# sensor_node_v0_03.net
KiCad netlist of a schematic drawn in EAGLE
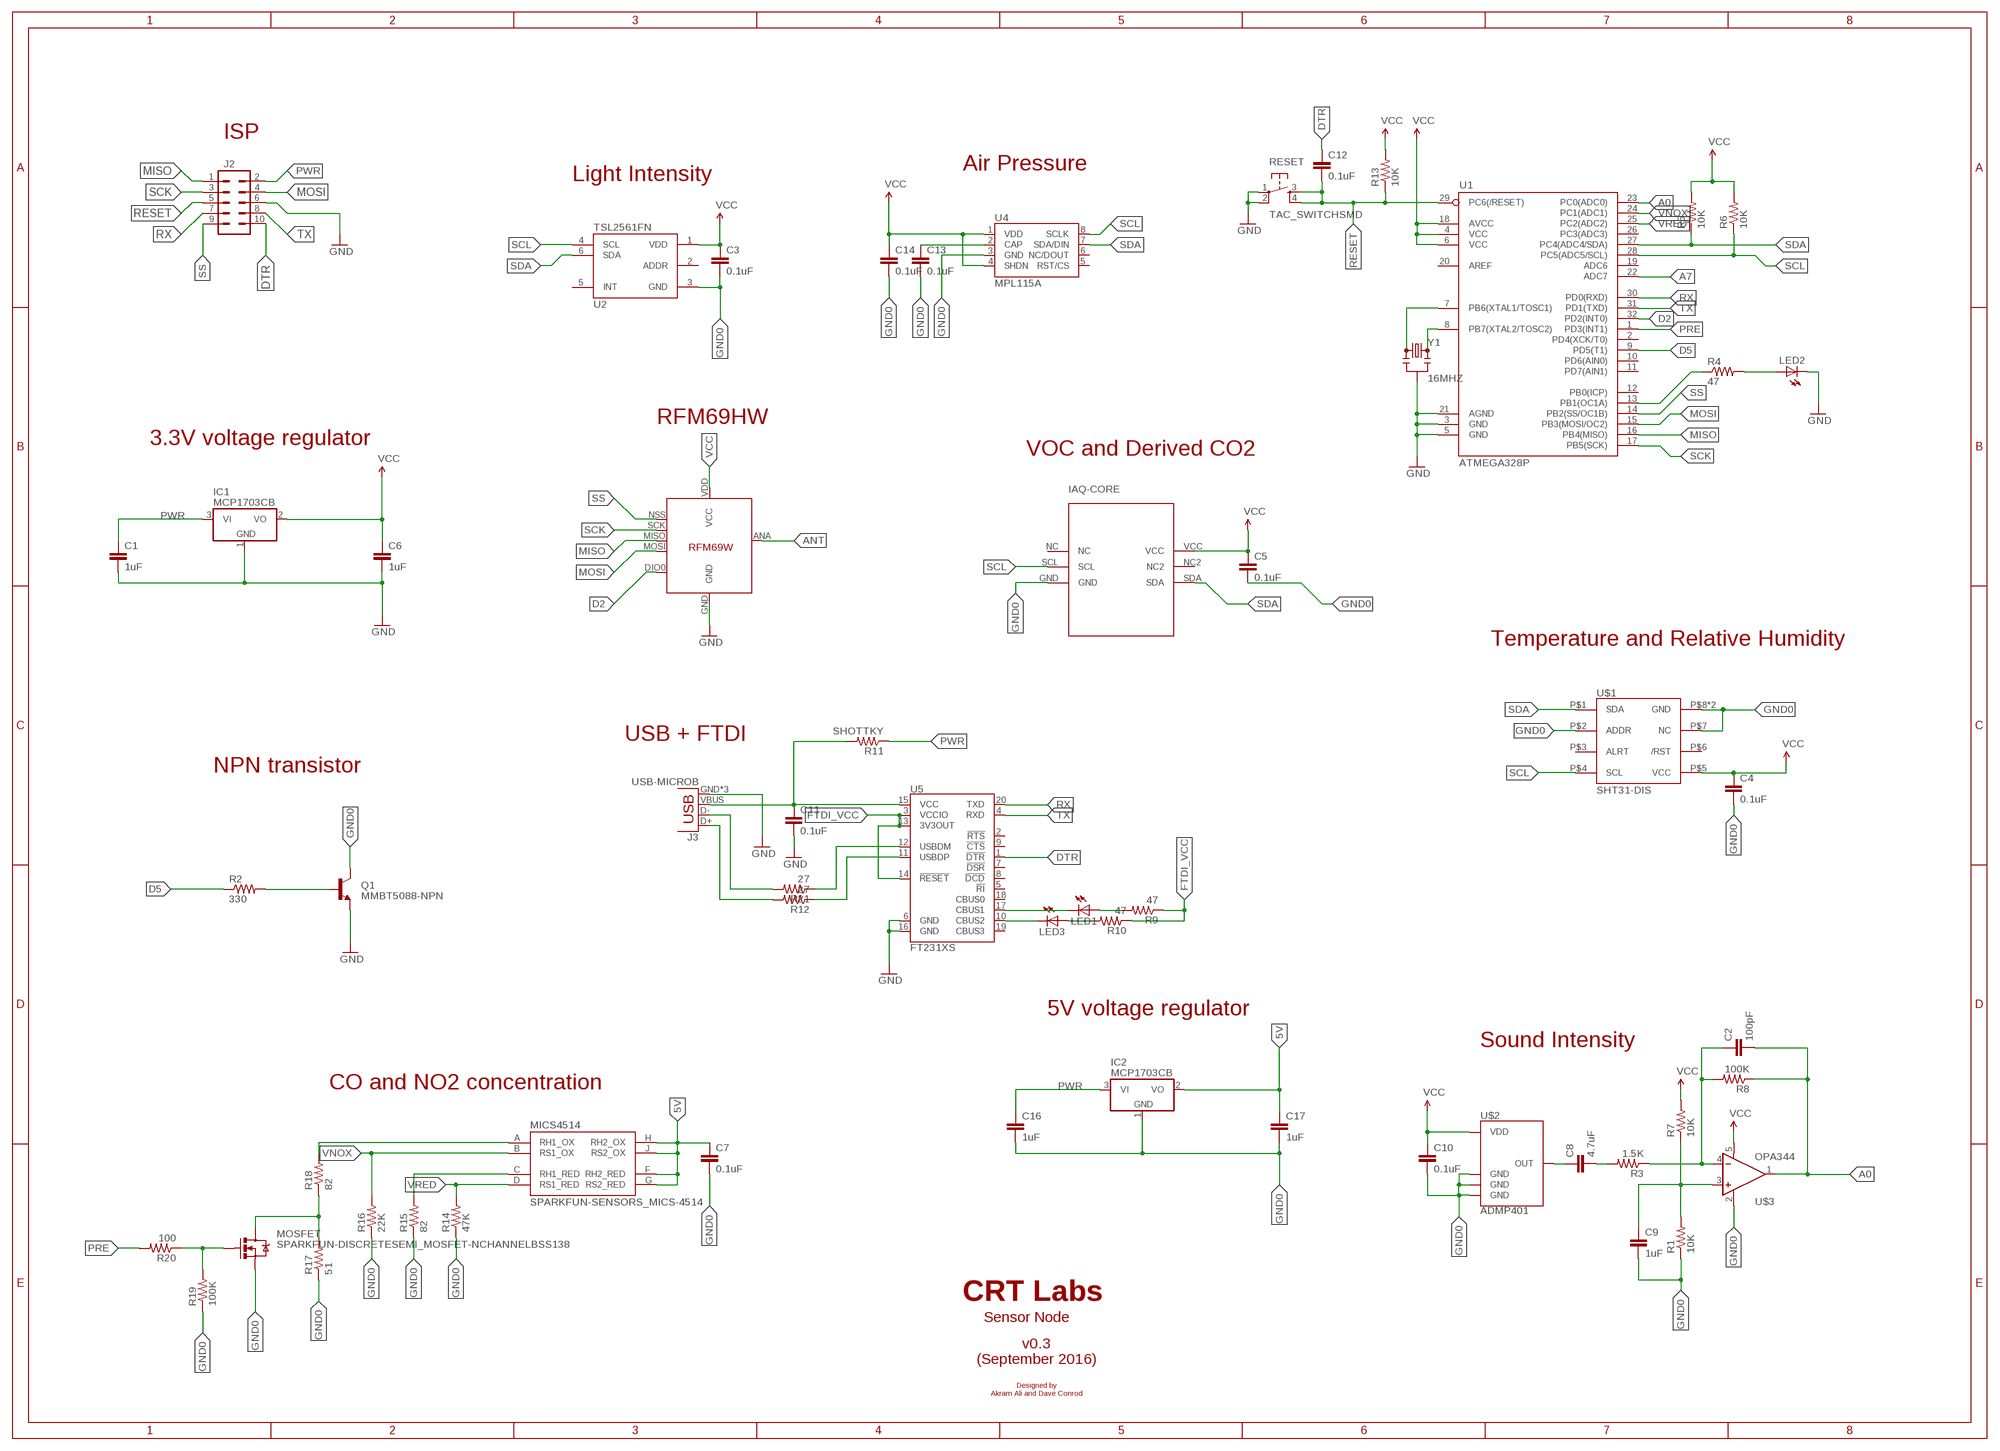
[diagram p0: schematic, sheet 1]

(export (version "E")
  (design (tool "Eeschema 10.0.6"))
  (components
    (comp (ref "C1")
      (value "1uF")
      (footprint "eagle-import:0805")
      (libsource (lib "eagle-import") (part "CAP0805"))
    )
    (comp (ref "C2")
      (value "100pF")
      (footprint "eagle-import:0805")
      (libsource (lib "eagle-import") (part "CAP0805"))
    )
    (comp (ref "C3")
      (value "0.1uF")
      (footprint "eagle-import:0805")
      (libsource (lib "eagle-import") (part "SparkFun-Passives_CAP0805"))
    )
    (comp (ref "C4")
      (value "0.1uF")
      (footprint "eagle-import:0805")
      (libsource (lib "eagle-import") (part "SparkFun-Passives_CAP0805"))
    )
    (comp (ref "C5")
      (value "0.1uF")
      (footprint "eagle-import:0805")
      (libsource (lib "eagle-import") (part "SparkFun-Passives_CAP0805"))
    )
    (comp (ref "C6")
      (value "1uF")
      (footprint "eagle-import:0805")
      (libsource (lib "eagle-import") (part "CAP0805"))
    )
    (comp (ref "C7")
      (value "0.1uF")
      (footprint "eagle-import:0805")
      (libsource (lib "eagle-import") (part "SparkFun-Passives_CAP0805"))
    )
    (comp (ref "C8")
      (value "4.7uF")
      (footprint "eagle-import:0805")
      (libsource (lib "eagle-import") (part "CAP0805"))
    )
    (comp (ref "C9")
      (value "1uF")
      (footprint "eagle-import:0805")
      (libsource (lib "eagle-import") (part "CAP0805"))
    )
    (comp (ref "C10")
      (value "0.1uF")
      (footprint "eagle-import:0805")
      (libsource (lib "eagle-import") (part "CAP0805"))
    )
    (comp (ref "C11")
      (value "0.1uF")
      (footprint "eagle-import:0805")
      (libsource (lib "eagle-import") (part "CAP0805"))
    )
    (comp (ref "C12")
      (value "0.1uF")
      (footprint "eagle-import:0805")
      (libsource (lib "eagle-import") (part "SparkFun-Passives_CAP0805"))
    )
    (comp (ref "C13")
      (value "0.1uF")
      (footprint "eagle-import:0805")
      (libsource (lib "eagle-import") (part "SparkFun-Passives_CAP0805"))
    )
    (comp (ref "C14")
      (value "0.1uF")
      (footprint "eagle-import:0805")
      (libsource (lib "eagle-import") (part "SparkFun-Passives_CAP0805"))
    )
    (comp (ref "C16")
      (value "1uF")
      (footprint "eagle-import:0805")
      (libsource (lib "eagle-import") (part "CAP0805"))
    )
    (comp (ref "C17")
      (value "1uF")
      (footprint "eagle-import:0805")
      (libsource (lib "eagle-import") (part "CAP0805"))
    )
    (comp (ref "IAQ-CORE")
      (value "IAQ-CORE")
      (footprint "eagle-import:IAQ-CORE")
      (fields (field (name "MPN") "IAQ CORE"))
      (libsource (lib "eagle-import") (part "IAQ-CORE"))
    )
    (comp (ref "IC1")
      (value "MCP1703CB")
      (footprint "eagle-import:SOT23")
      (fields (field (name "MPN") "MCP1703T-2502E/CB"))
      (libsource (lib "eagle-import") (part "MCP1703CB"))
    )
    (comp (ref "IC2")
      (value "MCP1703CB")
      (footprint "eagle-import:SOT23")
      (fields (field (name "MPN") "MCP1703T-2502E/CB"))
      (libsource (lib "eagle-import") (part "MCP1703CB"))
    )
    (comp (ref "J2")
      (value "M05X2PTH")
      (footprint "eagle-import:AVR_ICSP")
      (libsource (lib "eagle-import") (part "M05X2PTH"))
    )
    (comp (ref "J3")
      (value "USB-MICROB")
      (footprint "eagle-import:USB-MICROB")
      (libsource (lib "eagle-import") (part "USB-MICROB"))
    )
    (comp (ref "LED1")
      (value "LEDCHIPLED_0805")
      (footprint "eagle-import:CHIPLED_0805")
      (libsource (lib "eagle-import") (part "LEDCHIPLED_0805"))
    )
    (comp (ref "LED2")
      (value "LEDCHIPLED_0805")
      (footprint "eagle-import:CHIPLED_0805")
      (libsource (lib "eagle-import") (part "LEDCHIPLED_0805"))
    )
    (comp (ref "LED3")
      (value "LEDCHIPLED_0805")
      (footprint "eagle-import:CHIPLED_0805")
      (libsource (lib "eagle-import") (part "LEDCHIPLED_0805"))
    )
    (comp (ref "MICS4514")
      (value "SPARKFUN-SENSORS_MICS-4514")
      (footprint "eagle-import:SPARKFUN-SENSORS_MICS_10-SMD")
      (libsource (lib "eagle-import") (part "SPARKFUN-SENSORS_MICS-4514"))
    )
    (comp (ref "MOSFET")
      (value "SPARKFUN-DISCRETESEMI_MOSFET-NCHANNELBSS138")
      (footprint "eagle-import:SPARKFUN-DISCRETESEMI_SOT23-3")
      (libsource (lib "eagle-import") (part "SPARKFUN-DISCRETESEMI_MOSFET-NCHANNELBSS138"))
    )
    (comp (ref "Q1")
      (value "MMBT5088-NPN")
      (footprint "eagle-import:SOT23-3")
      (libsource (lib "eagle-import") (part "TRANSISTOR_NPNMMBT5088"))
    )
    (comp (ref "R1")
      (value "10K")
      (footprint "eagle-import:0805")
      (libsource (lib "eagle-import") (part "RESISTOR0805-RES"))
    )
    (comp (ref "R2")
      (value "330")
      (footprint "eagle-import:0805")
      (libsource (lib "eagle-import") (part "RESISTOR0805-RES"))
    )
    (comp (ref "R3")
      (value "1.5K")
      (footprint "eagle-import:0805")
      (libsource (lib "eagle-import") (part "RESISTOR0805-RES"))
    )
    (comp (ref "R4")
      (value "47")
      (footprint "eagle-import:0805")
      (libsource (lib "eagle-import") (part "SparkFun-Resistors_RESISTOR0805-RES"))
    )
    (comp (ref "R5")
      (value "10K")
      (footprint "eagle-import:0805")
      (libsource (lib "eagle-import") (part "SparkFun-Resistors_RESISTOR0805-RES"))
    )
    (comp (ref "R6")
      (value "10K")
      (footprint "eagle-import:0805")
      (libsource (lib "eagle-import") (part "SparkFun-Resistors_RESISTOR0805-RES"))
    )
    (comp (ref "R7")
      (value "10K")
      (footprint "eagle-import:0805")
      (libsource (lib "eagle-import") (part "RESISTOR0805-RES"))
    )
    (comp (ref "R8")
      (value "100K")
      (footprint "eagle-import:0805")
      (libsource (lib "eagle-import") (part "RESISTOR0805-RES"))
    )
    (comp (ref "R9")
      (value "47")
      (footprint "eagle-import:0805")
      (libsource (lib "eagle-import") (part "RESISTOR0805-RES"))
    )
    (comp (ref "R10")
      (value "47")
      (footprint "eagle-import:0805")
      (libsource (lib "eagle-import") (part "RESISTOR0805-RES"))
    )
    (comp (ref "R11")
      (value "SHOTTKY")
      (footprint "eagle-import:0805")
      (libsource (lib "eagle-import") (part "RESISTOR0805-RES"))
    )
    (comp (ref "R12")
      (value "27")
      (footprint "eagle-import:0805")
      (libsource (lib "eagle-import") (part "RESISTOR0805-RES"))
    )
    (comp (ref "R13")
      (value "10K")
      (footprint "eagle-import:0805")
      (libsource (lib "eagle-import") (part "RESISTOR0805-RES"))
    )
    (comp (ref "R14")
      (value "47K")
      (footprint "eagle-import:0805")
      (libsource (lib "eagle-import") (part "RESISTOR0805-RES"))
    )
    (comp (ref "R15")
      (value "82")
      (footprint "eagle-import:0805")
      (libsource (lib "eagle-import") (part "RESISTOR0805-RES"))
    )
    (comp (ref "R16")
      (value "22K")
      (footprint "eagle-import:0805")
      (libsource (lib "eagle-import") (part "RESISTOR0805-RES"))
    )
    (comp (ref "R17")
      (value "51")
      (footprint "eagle-import:0805")
      (libsource (lib "eagle-import") (part "RESISTOR0805-RES"))
    )
    (comp (ref "R18")
      (value "82")
      (footprint "eagle-import:0805")
      (libsource (lib "eagle-import") (part "RESISTOR0805-RES"))
    )
    (comp (ref "R19")
      (value "100K")
      (footprint "eagle-import:0805")
      (libsource (lib "eagle-import") (part "RESISTOR0805-RES"))
    )
    (comp (ref "R20")
      (value "100")
      (footprint "eagle-import:0805")
      (libsource (lib "eagle-import") (part "RESISTOR0805-RES"))
    )
    (comp (ref "R21")
      (value "27")
      (footprint "eagle-import:0805")
      (libsource (lib "eagle-import") (part "RESISTOR0805-RES"))
    )
    (comp (ref "RESET")
      (value "TAC_SWITCHSMD")
      (footprint "eagle-import:TACTILE-SWITCH-SMD")
      (libsource (lib "eagle-import") (part "TAC_SWITCHSMD"))
    )
    (comp (ref "U$1")
      (value "SHT31-DIS")
      (footprint "eagle-import:SHT3X")
      (fields (field (name "MPN") "SHT31-DIS-B"))
      (libsource (lib "eagle-import") (part "SHT31-DIS"))
    )
    (comp (ref "U$2")
      (value "ADMP401")
      (footprint "eagle-import:ADMP401")
      (libsource (lib "eagle-import") (part "ADMP401"))
    )
    (comp (ref "U$3")
      (value "OPA344")
      (footprint "eagle-import:SOT23-5")
      (libsource (lib "eagle-import") (part "OPA344"))
    )
    (comp (ref "U$4")
      (value "RFM69HW")
      (footprint "eagle-import:LOWPOWERLAB_RFM69W-MINPADS")
      (libsource (lib "eagle-import") (part "LOWPOWERLAB_RFM69"))
    )
    (comp (ref "U1")
      (value "ATMEGA328P")
      (footprint "eagle-import:TQFP32-08")
      (fields (field (name "MPN") "ATMEGA328PB-AU"))
      (libsource (lib "eagle-import") (part "ATMEGA328P_TQFP"))
    )
    (comp (ref "U2")
      (value "TSL2561FN")
      (footprint "eagle-import:FN-6")
      (fields (field (name "MANF") "AMS-TAOS-USA-Inc."))
      (libsource (lib "eagle-import") (part "TSL2561FN"))
    )
    (comp (ref "U4")
      (value "MPL115A")
      (footprint "eagle-import:LGA8")
      (libsource (lib "eagle-import") (part "MPL115A"))
    )
    (comp (ref "U5")
      (value "FT231XS")
      (footprint "eagle-import:SSOP20_L")
      (libsource (lib "eagle-import") (part "FT231XS"))
    )
    (comp (ref "Y1")
      (value "16MHZ")
      (footprint "eagle-import:RESONATOR-SMD")
      (libsource (lib "eagle-import") (part "RESONATOR16MHZ"))
    )
  )
  (nets
    (net (code "1") (name "5V") (class "Default")
      (node (ref "C17") (pin "1") (pinfunction "1_1") (pintype "passive"))
      (node (ref "C7") (pin "1") (pinfunction "1_1") (pintype "passive"))
      (node (ref "IC2") (pin "2") (pinfunction "VO_2") (pintype "passive"))
      (node (ref "MICS4514") (pin "F") (pinfunction "RH2_RED_F") (pintype "bidirectional"))
      (node (ref "MICS4514") (pin "G") (pinfunction "RS2_RED_G") (pintype "bidirectional"))
      (node (ref "MICS4514") (pin "H") (pinfunction "RH2_OX_H") (pintype "bidirectional"))
      (node (ref "MICS4514") (pin "J") (pinfunction "RS2_OX_J") (pintype "bidirectional"))
    )
    (net (code "2") (name "A0") (class "Default")
      (node (ref "C2") (pin "2") (pinfunction "2_2") (pintype "passive"))
      (node (ref "R8") (pin "1") (pinfunction "1_1") (pintype "passive"))
      (node (ref "U$3") (pin "1") (pinfunction "OUT_1") (pintype "output"))
      (node (ref "U1") (pin "23") (pinfunction "PC0(ADC0)_23") (pintype "bidirectional"))
    )
    (net (code "3") (name "A7") (class "Default")
      (node (ref "U1") (pin "22") (pinfunction "ADC7_22") (pintype "bidirectional"))
    )
    (net (code "4") (name "ANT") (class "Default")
      (node (ref "U$4") (pin "ANA") (pinfunction "ANT_ANA") (pintype "passive"))
    )
    (net (code "5") (name "D2") (class "Default")
      (node (ref "U$4") (pin "DIO0") (pinfunction "DIO0_DIO0") (pintype "open_collector"))
      (node (ref "U1") (pin "32") (pinfunction "PD2(INT0)_32") (pintype "bidirectional"))
    )
    (net (code "6") (name "D5") (class "Default")
      (node (ref "R2") (pin "1") (pinfunction "1_1") (pintype "passive"))
      (node (ref "U1") (pin "9") (pinfunction "PD5(T1)_9") (pintype "bidirectional"))
    )
    (net (code "7") (name "DTR") (class "Default")
      (node (ref "C12") (pin "1") (pinfunction "1_1") (pintype "passive"))
      (node (ref "J2") (pin "10") (pinfunction "10_10") (pintype "passive"))
      (node (ref "U5") (pin "1") (pinfunction "~{DTR}_1") (pintype "bidirectional"))
    )
    (net (code "8") (name "FTDI_VCC") (class "Default")
      (node (ref "R10") (pin "1") (pinfunction "1_1") (pintype "passive"))
      (node (ref "R9") (pin "1") (pinfunction "1_1") (pintype "passive"))
      (node (ref "U5") (pin "13") (pinfunction "3V3OUT_13") (pintype "bidirectional"))
      (node (ref "U5") (pin "14") (pinfunction "~{RESET}_14") (pintype "bidirectional"))
      (node (ref "U5") (pin "3") (pinfunction "VCCIO_3") (pintype "bidirectional"))
    )
    (net (code "9") (name "GND") (class "Default")
      (node (ref "C1") (pin "2") (pinfunction "2_2") (pintype "passive"))
      (node (ref "C11") (pin "2") (pinfunction "2_2") (pintype "passive"))
      (node (ref "C6") (pin "2") (pinfunction "2_2") (pintype "passive"))
      (node (ref "IC1") (pin "1") (pinfunction "GND_1") (pintype "passive"))
      (node (ref "J2") (pin "6") (pinfunction "6_6") (pintype "passive"))
      (node (ref "J3") (pin "GND") (pinfunction "GND_GND") (pintype "bidirectional"))
      (node (ref "J3") (pin "MT1") (pinfunction "GND_MT1") (pintype "bidirectional"))
      (node (ref "J3") (pin "MT2") (pinfunction "GND_MT2") (pintype "bidirectional"))
      (node (ref "LED2") (pin "C") (pinfunction "C_C") (pintype "passive"))
      (node (ref "Q1") (pin "2") (pinfunction "E_2") (pintype "passive"))
      (node (ref "RESET") (pin "1") (pinfunction "1_1") (pintype "passive"))
      (node (ref "RESET") (pin "2") (pinfunction "2_2") (pintype "passive"))
      (node (ref "U$4") (pin "GND") (pinfunction "GND_GND") (pintype "power_in"))
      (node (ref "U1") (pin "21") (pinfunction "AGND_21") (pintype "bidirectional"))
      (node (ref "U1") (pin "3") (pinfunction "GND_3") (pintype "bidirectional"))
      (node (ref "U1") (pin "5") (pinfunction "GND_5") (pintype "bidirectional"))
      (node (ref "U5") (pin "16") (pinfunction "GND_16") (pintype "bidirectional"))
      (node (ref "U5") (pin "6") (pinfunction "GND_6") (pintype "bidirectional"))
      (node (ref "Y1") (pin "2") (pinfunction "2_2") (pintype "passive"))
    )
    (net (code "10") (name "GND0") (class "Default")
      (node (ref "C10") (pin "2") (pinfunction "2_2") (pintype "passive"))
      (node (ref "C13") (pin "2") (pinfunction "2_2") (pintype "passive"))
      (node (ref "C14") (pin "2") (pinfunction "2_2") (pintype "passive"))
      (node (ref "C16") (pin "2") (pinfunction "2_2") (pintype "passive"))
      (node (ref "C17") (pin "2") (pinfunction "2_2") (pintype "passive"))
      (node (ref "C3") (pin "2") (pinfunction "2_2") (pintype "passive"))
      (node (ref "C4") (pin "2") (pinfunction "2_2") (pintype "passive"))
      (node (ref "C5") (pin "2") (pinfunction "2_2") (pintype "passive"))
      (node (ref "C7") (pin "2") (pinfunction "2_2") (pintype "passive"))
      (node (ref "C9") (pin "2") (pinfunction "2_2") (pintype "passive"))
      (node (ref "IAQ-CORE") (pin "GND") (pinfunction "GND_GND") (pintype "bidirectional"))
      (node (ref "IC2") (pin "1") (pinfunction "GND_1") (pintype "passive"))
      (node (ref "MOSFET") (pin "2") (pinfunction "S_2") (pintype "passive"))
      (node (ref "Q1") (pin "3") (pinfunction "C_3") (pintype "passive"))
      (node (ref "R1") (pin "1") (pinfunction "1_1") (pintype "passive"))
      (node (ref "R14") (pin "1") (pinfunction "1_1") (pintype "passive"))
      (node (ref "R15") (pin "1") (pinfunction "1_1") (pintype "passive"))
      (node (ref "R16") (pin "1") (pinfunction "1_1") (pintype "passive"))
      (node (ref "R17") (pin "1") (pinfunction "1_1") (pintype "passive"))
      (node (ref "R19") (pin "1") (pinfunction "1_1") (pintype "passive"))
      (node (ref "U$1") (pin "P$2") (pinfunction "ADDR_P$2") (pintype "bidirectional"))
      (node (ref "U$1") (pin "P$7") (pinfunction "NC_P$7") (pintype "bidirectional"))
      (node (ref "U$1") (pin "P$8") (pinfunction "GND_P$8") (pintype "bidirectional"))
      (node (ref "U$1") (pin "PAD") (pinfunction "GND_PAD") (pintype "bidirectional"))
      (node (ref "U$2") (pin "2") (pinfunction "GND_2") (pintype "bidirectional"))
      (node (ref "U$2") (pin "4") (pinfunction "GND_4") (pintype "bidirectional"))
      (node (ref "U$2") (pin "6") (pinfunction "GND_6") (pintype "bidirectional"))
      (node (ref "U$3") (pin "2") (pinfunction "V-_2") (pintype "power_in"))
      (node (ref "U2") (pin "3") (pinfunction "GND_3") (pintype "power_in"))
      (node (ref "U4") (pin "3") (pinfunction "GND_3") (pintype "bidirectional"))
    )
    (net (code "11") (name "MISO") (class "Default")
      (node (ref "J2") (pin "1") (pinfunction "1_1") (pintype "passive"))
      (node (ref "U$4") (pin "MISO") (pinfunction "MISO_MISO") (pintype "input"))
      (node (ref "U1") (pin "16") (pinfunction "PB4(MISO)_16") (pintype "bidirectional"))
    )
    (net (code "12") (name "MOSI") (class "Default")
      (node (ref "J2") (pin "4") (pinfunction "4_4") (pintype "passive"))
      (node (ref "U$4") (pin "MOSI") (pinfunction "MOSI_MOSI") (pintype "output"))
      (node (ref "U1") (pin "15") (pinfunction "PB3(MOSI/OC2)_15") (pintype "bidirectional"))
    )
    (net (code "13") (name "Net-(C8-Pad2)") (class "Default")
      (node (ref "C8") (pin "2") (pinfunction "2_2") (pintype "passive"))
      (node (ref "R3") (pin "2") (pinfunction "2_2") (pintype "passive"))
    )
    (net (code "14") (name "Net-(J3-PadD+)") (class "Default")
      (node (ref "J3") (pin "D+") (pinfunction "D+_D+") (pintype "bidirectional"))
      (node (ref "R12") (pin "2") (pinfunction "2_2") (pintype "passive"))
    )
    (net (code "15") (name "Net-(J3-PadD-)") (class "Default")
      (node (ref "J3") (pin "D-") (pinfunction "D-_D-") (pintype "bidirectional"))
      (node (ref "R21") (pin "2") (pinfunction "2_2") (pintype "passive"))
    )
    (net (code "16") (name "Net-(LED1-PadA)") (class "Default")
      (node (ref "LED1") (pin "A") (pinfunction "A_A") (pintype "passive"))
      (node (ref "R9") (pin "2") (pinfunction "2_2") (pintype "passive"))
    )
    (net (code "17") (name "Net-(LED2-PadA)") (class "Default")
      (node (ref "LED2") (pin "A") (pinfunction "A_A") (pintype "passive"))
      (node (ref "R4") (pin "2") (pinfunction "2_2") (pintype "passive"))
    )
    (net (code "18") (name "Net-(LED3-PadA)") (class "Default")
      (node (ref "LED3") (pin "A") (pinfunction "A_A") (pintype "passive"))
      (node (ref "R10") (pin "2") (pinfunction "2_2") (pintype "passive"))
    )
    (net (code "19") (name "Net-(MICS4514-RH1_OX)") (class "Default")
      (node (ref "MICS4514") (pin "A") (pinfunction "RH1_OX_A") (pintype "bidirectional"))
      (node (ref "R18") (pin "2") (pinfunction "2_2") (pintype "passive"))
    )
    (net (code "20") (name "Net-(MICS4514-RH1_RED)") (class "Default")
      (node (ref "MICS4514") (pin "C") (pinfunction "RH1_RED_C") (pintype "bidirectional"))
      (node (ref "R15") (pin "2") (pinfunction "2_2") (pintype "passive"))
    )
    (net (code "21") (name "Net-(MOSFET-D)") (class "Default")
      (node (ref "MOSFET") (pin "3") (pinfunction "D_3") (pintype "passive"))
      (node (ref "R17") (pin "2") (pinfunction "2_2") (pintype "passive"))
      (node (ref "R18") (pin "1") (pinfunction "1_1") (pintype "passive"))
    )
    (net (code "22") (name "Net-(MOSFET-G)") (class "Default")
      (node (ref "MOSFET") (pin "1") (pinfunction "G_1") (pintype "passive"))
      (node (ref "R19") (pin "2") (pinfunction "2_2") (pintype "passive"))
      (node (ref "R20") (pin "1") (pinfunction "1_1") (pintype "passive"))
    )
    (net (code "23") (name "Net-(Q1-B)") (class "Default")
      (node (ref "Q1") (pin "1") (pinfunction "B_1") (pintype "passive"))
      (node (ref "R2") (pin "2") (pinfunction "2_2") (pintype "passive"))
    )
    (net (code "24") (name "Net-(U$2-OUT)") (class "Default")
      (node (ref "C8") (pin "1") (pinfunction "1_1") (pintype "passive"))
      (node (ref "U$2") (pin "1") (pinfunction "OUT_1") (pintype "bidirectional"))
    )
    (net (code "25") (name "Net-(U$3-+IN)") (class "Default")
      (node (ref "C9") (pin "1") (pinfunction "1_1") (pintype "passive"))
      (node (ref "R1") (pin "2") (pinfunction "2_2") (pintype "passive"))
      (node (ref "R7") (pin "1") (pinfunction "1_1") (pintype "passive"))
      (node (ref "U$3") (pin "3") (pinfunction "+IN_3") (pintype "input"))
    )
    (net (code "26") (name "Net-(U$3--IN)") (class "Default")
      (node (ref "C2") (pin "1") (pinfunction "1_1") (pintype "passive"))
      (node (ref "R3") (pin "1") (pinfunction "1_1") (pintype "passive"))
      (node (ref "R8") (pin "2") (pinfunction "2_2") (pintype "passive"))
      (node (ref "U$3") (pin "4") (pinfunction "-IN_4") (pintype "input"))
    )
    (net (code "27") (name "Net-(U1-PB1(OC1A))") (class "Default")
      (node (ref "R4") (pin "1") (pinfunction "1_1") (pintype "passive"))
      (node (ref "U1") (pin "13") (pinfunction "PB1(OC1A)_13") (pintype "bidirectional"))
    )
    (net (code "28") (name "Net-(U1-PB6(XTAL1{slash}TOSC1))") (class "Default")
      (node (ref "U1") (pin "7") (pinfunction "PB6(XTAL1/TOSC1)_7") (pintype "bidirectional"))
      (node (ref "Y1") (pin "1") (pinfunction "1_1") (pintype "passive"))
    )
    (net (code "29") (name "Net-(U1-PB7(XTAL2{slash}TOSC2))") (class "Default")
      (node (ref "U1") (pin "8") (pinfunction "PB7(XTAL2/TOSC2)_8") (pintype "bidirectional"))
      (node (ref "Y1") (pin "3") (pinfunction "3_3") (pintype "passive"))
    )
    (net (code "30") (name "Net-(U4-CAP)") (class "Default")
      (node (ref "C13") (pin "1") (pinfunction "1_1") (pintype "passive"))
      (node (ref "U4") (pin "2") (pinfunction "CAP_2") (pintype "bidirectional"))
    )
    (net (code "31") (name "Net-(U5-CBUS1)") (class "Default")
      (node (ref "LED1") (pin "C") (pinfunction "C_C") (pintype "passive"))
      (node (ref "U5") (pin "17") (pinfunction "CBUS1_17") (pintype "bidirectional"))
    )
    (net (code "32") (name "Net-(U5-CBUS2)") (class "Default")
      (node (ref "LED3") (pin "C") (pinfunction "C_C") (pintype "passive"))
      (node (ref "U5") (pin "10") (pinfunction "CBUS2_10") (pintype "bidirectional"))
    )
    (net (code "33") (name "Net-(U5-USBDM)") (class "Default")
      (node (ref "R21") (pin "1") (pinfunction "1_1") (pintype "passive"))
      (node (ref "U5") (pin "12") (pinfunction "USBDM_12") (pintype "bidirectional"))
    )
    (net (code "34") (name "Net-(U5-USBDP)") (class "Default")
      (node (ref "R12") (pin "1") (pinfunction "1_1") (pintype "passive"))
      (node (ref "U5") (pin "11") (pinfunction "USBDP_11") (pintype "bidirectional"))
    )
    (net (code "35") (name "Net-(U5-VCC)") (class "Default")
      (node (ref "C11") (pin "1") (pinfunction "1_1") (pintype "passive"))
      (node (ref "J3") (pin "VBUS") (pinfunction "VBUS_VBUS") (pintype "bidirectional"))
      (node (ref "R11") (pin "2") (pinfunction "2_2") (pintype "passive"))
      (node (ref "U5") (pin "15") (pinfunction "VCC_15") (pintype "bidirectional"))
    )
    (net (code "36") (name "PRE") (class "Default")
      (node (ref "R20") (pin "2") (pinfunction "2_2") (pintype "passive"))
      (node (ref "U1") (pin "1") (pinfunction "PD3(INT1)_1") (pintype "bidirectional"))
    )
    (net (code "37") (name "PWR") (class "Default")
      (node (ref "C1") (pin "1") (pinfunction "1_1") (pintype "passive"))
      (node (ref "C16") (pin "1") (pinfunction "1_1") (pintype "passive"))
      (node (ref "IC1") (pin "3") (pinfunction "VI_3") (pintype "input"))
      (node (ref "IC2") (pin "3") (pinfunction "VI_3") (pintype "input"))
      (node (ref "J2") (pin "2") (pinfunction "2_2") (pintype "passive"))
      (node (ref "R11") (pin "1") (pinfunction "1_1") (pintype "passive"))
    )
    (net (code "38") (name "RESET") (class "Default")
      (node (ref "C12") (pin "2") (pinfunction "2_2") (pintype "passive"))
      (node (ref "J2") (pin "5") (pinfunction "5_5") (pintype "passive"))
      (node (ref "R13") (pin "1") (pinfunction "1_1") (pintype "passive"))
      (node (ref "RESET") (pin "3") (pinfunction "3_3") (pintype "passive"))
      (node (ref "RESET") (pin "4") (pinfunction "4_4") (pintype "passive"))
      (node (ref "U1") (pin "29") (pinfunction "PC6(/RESET)_29") (pintype "bidirectional"))
    )
    (net (code "39") (name "RX") (class "Default")
      (node (ref "J2") (pin "7") (pinfunction "7_7") (pintype "passive"))
      (node (ref "U1") (pin "30") (pinfunction "PD0(RXD)_30") (pintype "bidirectional"))
      (node (ref "U5") (pin "20") (pinfunction "TXD_20") (pintype "bidirectional"))
    )
    (net (code "40") (name "SCK") (class "Default")
      (node (ref "J2") (pin "3") (pinfunction "3_3") (pintype "passive"))
      (node (ref "U$4") (pin "SCK") (pinfunction "SCK_SCK") (pintype "input"))
      (node (ref "U1") (pin "17") (pinfunction "PB5(SCK)_17") (pintype "bidirectional"))
    )
    (net (code "41") (name "SCL") (class "Default")
      (node (ref "IAQ-CORE") (pin "SCL") (pinfunction "SCL_SCL") (pintype "bidirectional"))
      (node (ref "R6") (pin "1") (pinfunction "1_1") (pintype "passive"))
      (node (ref "U$1") (pin "P$4") (pinfunction "SCL_P$4") (pintype "bidirectional"))
      (node (ref "U1") (pin "28") (pinfunction "PC5(ADC5/SCL)_28") (pintype "bidirectional"))
      (node (ref "U2") (pin "4") (pinfunction "SCL_4") (pintype "input"))
      (node (ref "U4") (pin "8") (pinfunction "SCLK_8") (pintype "bidirectional"))
    )
    (net (code "42") (name "SDA") (class "Default")
      (node (ref "IAQ-CORE") (pin "SDA") (pinfunction "SDA_SDA") (pintype "bidirectional"))
      (node (ref "R5") (pin "1") (pinfunction "1_1") (pintype "passive"))
      (node (ref "U$1") (pin "P$1") (pinfunction "SDA_P$1") (pintype "bidirectional"))
      (node (ref "U1") (pin "27") (pinfunction "PC4(ADC4/SDA)_27") (pintype "bidirectional"))
      (node (ref "U2") (pin "6") (pinfunction "SDA_6") (pintype "bidirectional"))
      (node (ref "U4") (pin "7") (pinfunction "SDA/DIN_7") (pintype "bidirectional"))
    )
    (net (code "43") (name "SS") (class "Default")
      (node (ref "J2") (pin "9") (pinfunction "9_9") (pintype "passive"))
      (node (ref "U$4") (pin "NSS") (pinfunction "SEL_NSS") (pintype "input"))
      (node (ref "U1") (pin "14") (pinfunction "PB2(SS/OC1B)_14") (pintype "bidirectional"))
    )
    (net (code "44") (name "TX") (class "Default")
      (node (ref "J2") (pin "8") (pinfunction "8_8") (pintype "passive"))
      (node (ref "U1") (pin "31") (pinfunction "PD1(TXD)_31") (pintype "bidirectional"))
      (node (ref "U5") (pin "4") (pinfunction "RXD_4") (pintype "bidirectional"))
    )
    (net (code "45") (name "VCC") (class "Default")
      (node (ref "C10") (pin "1") (pinfunction "1_1") (pintype "passive"))
      (node (ref "C14") (pin "1") (pinfunction "1_1") (pintype "passive"))
      (node (ref "C3") (pin "1") (pinfunction "1_1") (pintype "passive"))
      (node (ref "C4") (pin "1") (pinfunction "1_1") (pintype "passive"))
      (node (ref "C5") (pin "1") (pinfunction "1_1") (pintype "passive"))
      (node (ref "C6") (pin "1") (pinfunction "1_1") (pintype "passive"))
      (node (ref "IAQ-CORE") (pin "VCC") (pinfunction "VCC_VCC") (pintype "bidirectional"))
      (node (ref "IC1") (pin "2") (pinfunction "VO_2") (pintype "passive"))
      (node (ref "R13") (pin "2") (pinfunction "2_2") (pintype "passive"))
      (node (ref "R5") (pin "2") (pinfunction "2_2") (pintype "passive"))
      (node (ref "R6") (pin "2") (pinfunction "2_2") (pintype "passive"))
      (node (ref "R7") (pin "2") (pinfunction "2_2") (pintype "passive"))
      (node (ref "U$1") (pin "P$5") (pinfunction "VCC_P$5") (pintype "bidirectional"))
      (node (ref "U$2") (pin "5") (pinfunction "VDD_5") (pintype "bidirectional"))
      (node (ref "U$3") (pin "5") (pinfunction "V+_5") (pintype "power_in"))
      (node (ref "U$4") (pin "VDD") (pinfunction "VCC_VDD") (pintype "power_in"))
      (node (ref "U1") (pin "18") (pinfunction "AVCC_18") (pintype "bidirectional"))
      (node (ref "U1") (pin "4") (pinfunction "VCC_4") (pintype "bidirectional"))
      (node (ref "U1") (pin "6") (pinfunction "VCC_6") (pintype "bidirectional"))
      (node (ref "U2") (pin "1") (pinfunction "VDD_1") (pintype "power_in"))
      (node (ref "U4") (pin "1") (pinfunction "VDD_1") (pintype "bidirectional"))
      (node (ref "U4") (pin "4") (pinfunction "SHDN_4") (pintype "bidirectional"))
    )
    (net (code "46") (name "VNOX") (class "Default")
      (node (ref "MICS4514") (pin "B") (pinfunction "RS1_OX_B") (pintype "bidirectional"))
      (node (ref "R16") (pin "2") (pinfunction "2_2") (pintype "passive"))
      (node (ref "U1") (pin "24") (pinfunction "PC1(ADC1)_24") (pintype "bidirectional"))
    )
    (net (code "47") (name "VRED") (class "Default")
      (node (ref "MICS4514") (pin "D") (pinfunction "RS1_RED_D") (pintype "bidirectional"))
      (node (ref "R14") (pin "2") (pinfunction "2_2") (pintype "passive"))
      (node (ref "U1") (pin "25") (pinfunction "PC2(ADC2)_25") (pintype "bidirectional"))
    )
    (net (code "48") (name "unconnected-(IAQ-CORE-PadNC)") (class "Default")
      (node (ref "IAQ-CORE") (pin "NC") (pinfunction "NC_NC") (pintype "bidirectional"))
    )
    (net (code "49") (name "unconnected-(IAQ-CORE-PadNC2)") (class "Default")
      (node (ref "IAQ-CORE") (pin "NC2") (pinfunction "NC2_NC2") (pintype "bidirectional"))
    )
    (net (code "50") (name "unconnected-(U$1-ALRT-PadP$3)") (class "Default")
      (node (ref "U$1") (pin "P$3") (pinfunction "ALRT_P$3") (pintype "bidirectional"))
    )
    (net (code "51") (name "unconnected-(U$1-{slash}RST-PadP$6)") (class "Default")
      (node (ref "U$1") (pin "P$6") (pinfunction "/RST_P$6") (pintype "bidirectional"))
    )
    (net (code "52") (name "unconnected-(U1-ADC6-Pad19)") (class "Default")
      (node (ref "U1") (pin "19") (pinfunction "ADC6_19") (pintype "bidirectional"))
    )
    (net (code "53") (name "unconnected-(U1-AREF-Pad20)") (class "Default")
      (node (ref "U1") (pin "20") (pinfunction "AREF_20") (pintype "bidirectional"))
    )
    (net (code "54") (name "unconnected-(U1-PB0(ICP)-Pad12)") (class "Default")
      (node (ref "U1") (pin "12") (pinfunction "PB0(ICP)_12") (pintype "bidirectional"))
    )
    (net (code "55") (name "unconnected-(U1-PC3(ADC3)-Pad26)") (class "Default")
      (node (ref "U1") (pin "26") (pinfunction "PC3(ADC3)_26") (pintype "bidirectional"))
    )
    (net (code "56") (name "unconnected-(U1-PD4(XCK{slash}T0)-Pad2)") (class "Default")
      (node (ref "U1") (pin "2") (pinfunction "PD4(XCK/T0)_2") (pintype "bidirectional"))
    )
    (net (code "57") (name "unconnected-(U1-PD6(AIN0)-Pad10)") (class "Default")
      (node (ref "U1") (pin "10") (pinfunction "PD6(AIN0)_10") (pintype "bidirectional"))
    )
    (net (code "58") (name "unconnected-(U1-PD7(AIN1)-Pad11)") (class "Default")
      (node (ref "U1") (pin "11") (pinfunction "PD7(AIN1)_11") (pintype "bidirectional"))
    )
    (net (code "59") (name "unconnected-(U2-ADDR-Pad2)") (class "Default")
      (node (ref "U2") (pin "2") (pinfunction "ADDR_2") (pintype "input"))
    )
    (net (code "60") (name "unconnected-(U2-INT-Pad5)") (class "Default")
      (node (ref "U2") (pin "5") (pinfunction "INT_5") (pintype "output"))
    )
    (net (code "61") (name "unconnected-(U4-NC{slash}DOUT-Pad6)") (class "Default")
      (node (ref "U4") (pin "6") (pinfunction "NC/DOUT_6") (pintype "bidirectional"))
    )
    (net (code "62") (name "unconnected-(U4-RST{slash}CS-Pad5)") (class "Default")
      (node (ref "U4") (pin "5") (pinfunction "RST/CS_5") (pintype "bidirectional"))
    )
    (net (code "63") (name "unconnected-(U5-CBUS0-Pad18)") (class "Default")
      (node (ref "U5") (pin "18") (pinfunction "CBUS0_18") (pintype "bidirectional"))
    )
    (net (code "64") (name "unconnected-(U5-CBUS3-Pad19)") (class "Default")
      (node (ref "U5") (pin "19") (pinfunction "CBUS3_19") (pintype "bidirectional"))
    )
    (net (code "65") (name "unconnected-(U5-~{CTS}-Pad9)") (class "Default")
      (node (ref "U5") (pin "9") (pinfunction "~{CTS}_9") (pintype "bidirectional"))
    )
    (net (code "66") (name "unconnected-(U5-~{DCD}-Pad8)") (class "Default")
      (node (ref "U5") (pin "8") (pinfunction "~{DCD}_8") (pintype "bidirectional"))
    )
    (net (code "67") (name "unconnected-(U5-~{DSR}-Pad7)") (class "Default")
      (node (ref "U5") (pin "7") (pinfunction "~{DSR}_7") (pintype "bidirectional"))
    )
    (net (code "68") (name "unconnected-(U5-~{RI}-Pad5)") (class "Default")
      (node (ref "U5") (pin "5") (pinfunction "~{RI}_5") (pintype "bidirectional"))
    )
    (net (code "69") (name "unconnected-(U5-~{RTS}-Pad2)") (class "Default")
      (node (ref "U5") (pin "2") (pinfunction "~{RTS}_2") (pintype "bidirectional"))
    )
  )
)
